# C-logo.net
KiCad netlist of a schematic drawn in EAGLE
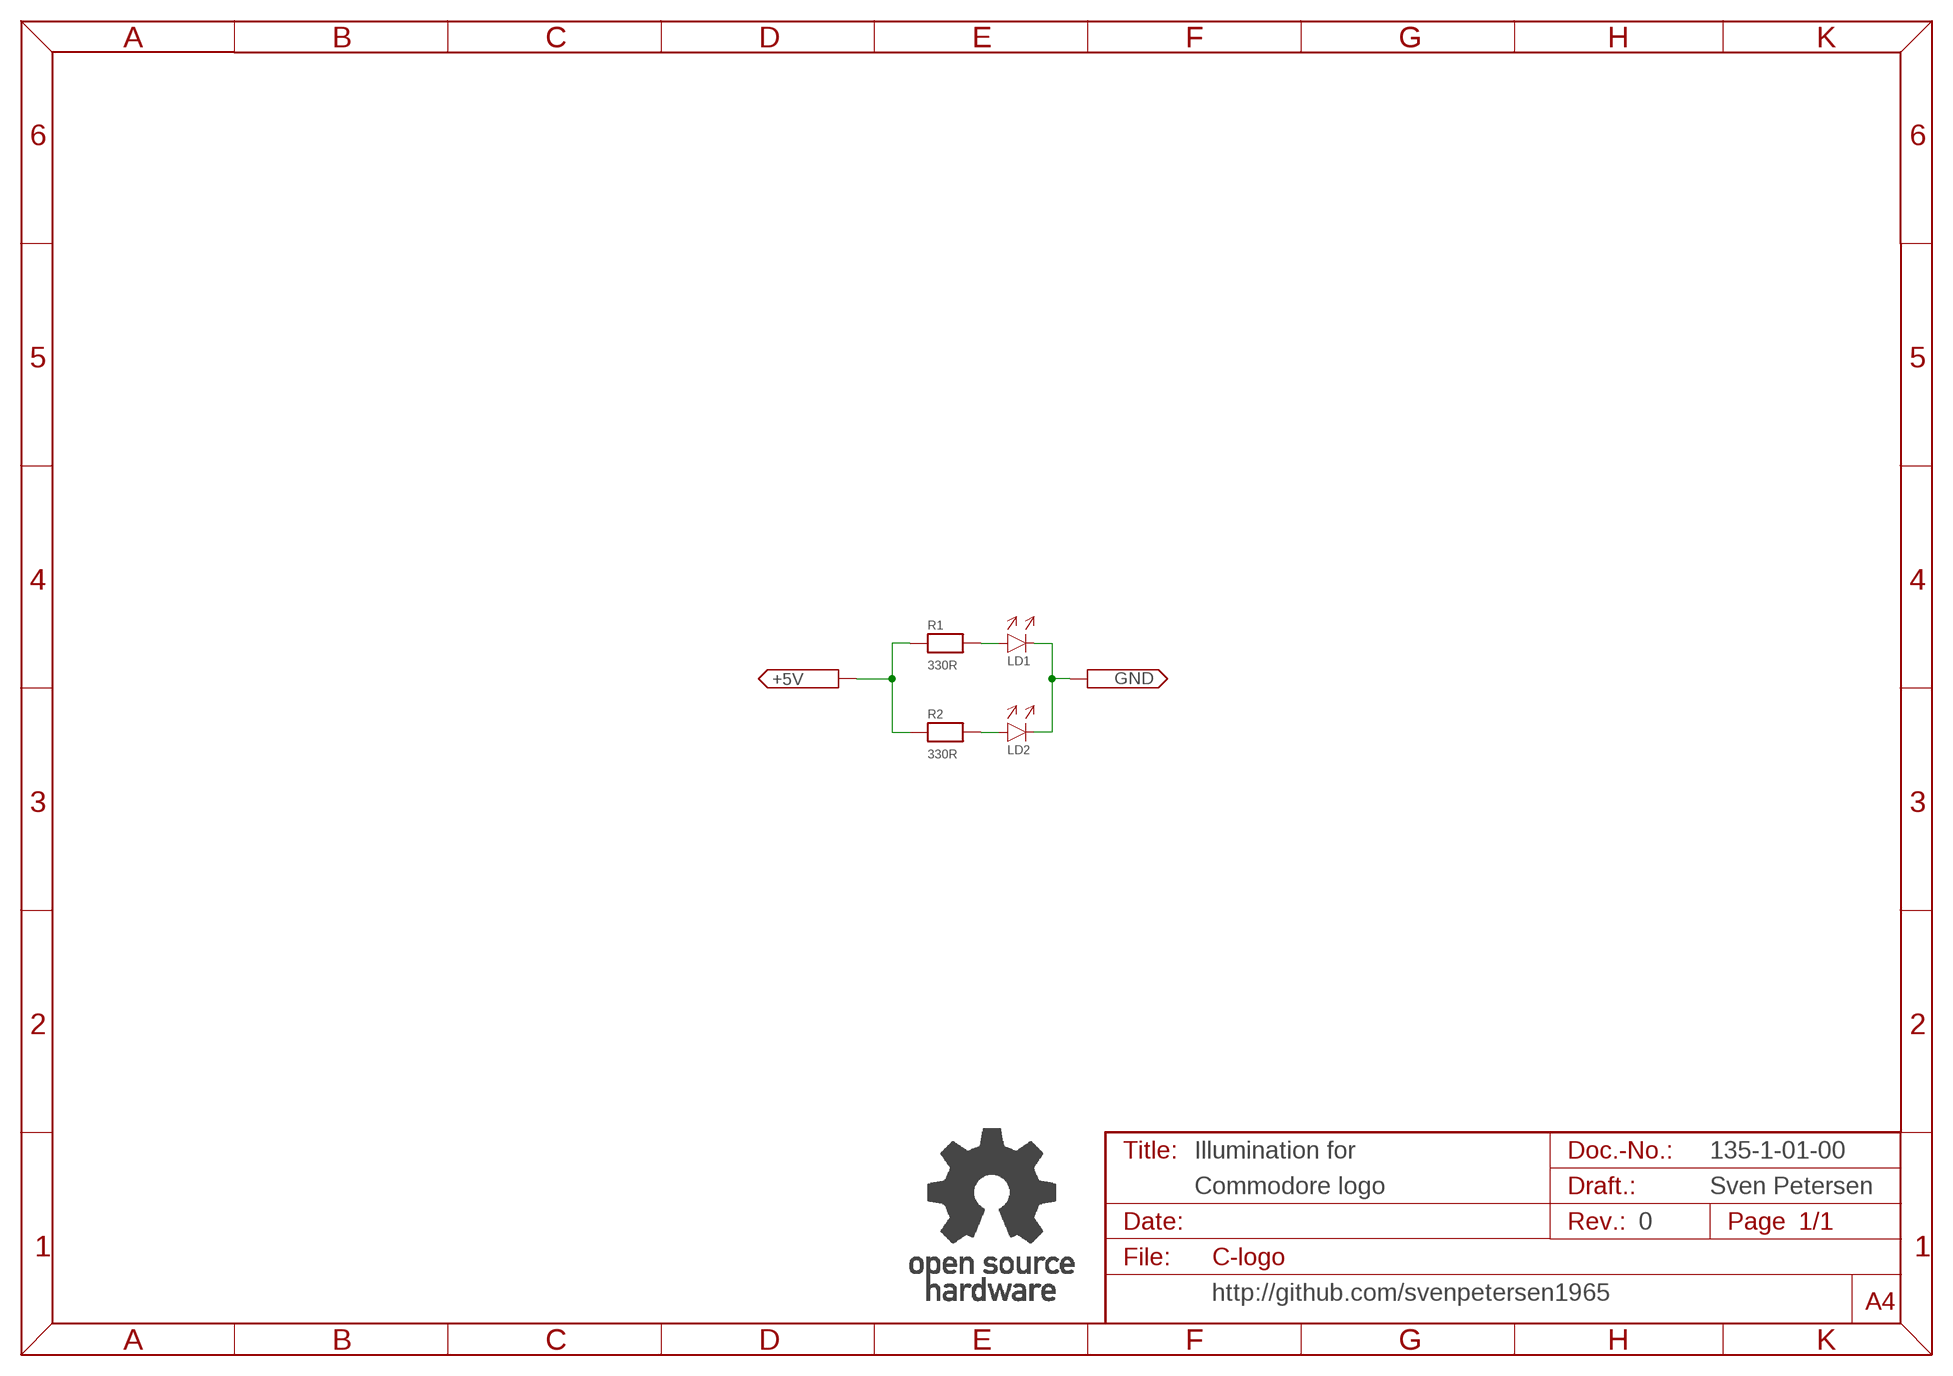
[diagram p0: schematic, sheet 1]

(export (version "E")
  (design (tool "Eeschema 10.0.6"))
  (components
    (comp (ref "+5V")
      (value "PAD1,0/AUTO")
      (footprint "eagle-import:1.0_AUTO")
      (libsource (lib "eagle-import") (part "PAD1,0/AUTO"))
    )
    (comp (ref "GND")
      (value "PAD1,0/AUTO")
      (footprint "eagle-import:1.0_AUTO")
      (libsource (lib "eagle-import") (part "PAD1,0/AUTO"))
    )
    (comp (ref "LD1")
      (value "5MM90°INSERTED")
      (footprint "eagle-import:5MM_90°")
      (libsource (lib "eagle-import") (part "5MM90°INSERTED"))
    )
    (comp (ref "LD2")
      (value "5MM90°INSERTED")
      (footprint "eagle-import:5MM_90°")
      (libsource (lib "eagle-import") (part "5MM90°INSERTED"))
    )
    (comp (ref "R1")
      (value "330R")
      (footprint "eagle-import:R-10")
      (libsource (lib "eagle-import") (part "RES04"))
    )
    (comp (ref "R2")
      (value "330R")
      (footprint "eagle-import:R-10")
      (libsource (lib "eagle-import") (part "RES04"))
    )
    (comp (ref "U$5")
      (value "OPEN_SOURCE_HW")
      (footprint "eagle-import:OPENHW")
      (libsource (lib "eagle-import") (part "OPEN_SOURCE_HW"))
    )
  )
  (nets
    (net (code "1") (name "Net-(+5V-Pad1)") (class "Default")
      (node (ref "+5V") (pin "1") (pinfunction "1_1") (pintype "passive"))
      (node (ref "R1") (pin "1") (pinfunction "1_1") (pintype "passive"))
      (node (ref "R2") (pin "1") (pinfunction "1_1") (pintype "passive"))
    )
    (net (code "2") (name "Net-(GND-Pad1)") (class "Default")
      (node (ref "GND") (pin "1") (pinfunction "1_1") (pintype "passive"))
      (node (ref "LD1") (pin "K") (pinfunction "K_K") (pintype "bidirectional"))
      (node (ref "LD2") (pin "K") (pinfunction "K_K") (pintype "bidirectional"))
    )
    (net (code "3") (name "Net-(LD1-PadA)") (class "Default")
      (node (ref "LD1") (pin "A") (pinfunction "A_A") (pintype "bidirectional"))
      (node (ref "R1") (pin "2") (pinfunction "2_2") (pintype "passive"))
    )
    (net (code "4") (name "Net-(LD2-PadA)") (class "Default")
      (node (ref "LD2") (pin "A") (pinfunction "A_A") (pintype "bidirectional"))
      (node (ref "R2") (pin "2") (pinfunction "2_2") (pintype "passive"))
    )
  )
)
